# Twintig-FCC-Host.net
KiCad netlist of a schematic drawn in Altium Designer
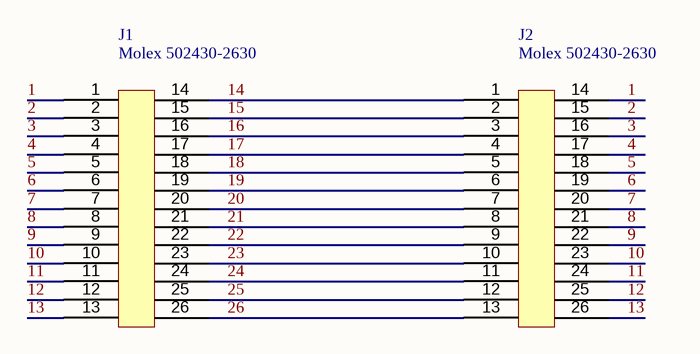
[diagram p0: Twintig-FCC-Host.SchDoc]

(export (version "E")
  (design (tool "Eeschema 10.0.6"))
  (components
    (comp (ref "J1")
      (value "Molex 502430-2630")
      (footprint "Molex 502430-2630")
      (libsource (lib "x-io") (part "Molex 502430-2630"))
    )
    (comp (ref "J2")
      (value "Molex 502430-2630")
      (footprint "Molex 502430-2630")
      (libsource (lib "x-io") (part "Molex 502430-2630"))
    )
  )
  (nets
    (net (code "1") (name "/1") (class "Default")
      (node (ref "J1") (pin "1") (pinfunction "1_1") (pintype "passive"))
      (node (ref "J2") (pin "14") (pinfunction "14_14") (pintype "passive"))
    )
    (net (code "2") (name "/2") (class "Default")
      (node (ref "J1") (pin "2") (pinfunction "2_2") (pintype "passive"))
      (node (ref "J2") (pin "15") (pinfunction "15_15") (pintype "passive"))
    )
    (net (code "3") (name "/3") (class "Default")
      (node (ref "J1") (pin "3") (pinfunction "3_3") (pintype "passive"))
      (node (ref "J2") (pin "16") (pinfunction "16_16") (pintype "passive"))
    )
    (net (code "4") (name "/4") (class "Default")
      (node (ref "J1") (pin "4") (pinfunction "4_4") (pintype "passive"))
      (node (ref "J2") (pin "17") (pinfunction "17_17") (pintype "passive"))
    )
    (net (code "5") (name "/5") (class "Default")
      (node (ref "J1") (pin "5") (pinfunction "5_5") (pintype "passive"))
      (node (ref "J2") (pin "18") (pinfunction "18_18") (pintype "passive"))
    )
    (net (code "6") (name "/6") (class "Default")
      (node (ref "J1") (pin "6") (pinfunction "6_6") (pintype "passive"))
      (node (ref "J2") (pin "19") (pinfunction "19_19") (pintype "passive"))
    )
    (net (code "7") (name "/7") (class "Default")
      (node (ref "J1") (pin "7") (pinfunction "7_7") (pintype "passive"))
      (node (ref "J2") (pin "20") (pinfunction "20_20") (pintype "passive"))
    )
    (net (code "8") (name "/8") (class "Default")
      (node (ref "J1") (pin "8") (pinfunction "8_8") (pintype "passive"))
      (node (ref "J2") (pin "21") (pinfunction "21_21") (pintype "passive"))
    )
    (net (code "9") (name "/9") (class "Default")
      (node (ref "J1") (pin "9") (pinfunction "9_9") (pintype "passive"))
      (node (ref "J2") (pin "22") (pinfunction "22_22") (pintype "passive"))
    )
    (net (code "10") (name "/10") (class "Default")
      (node (ref "J1") (pin "10") (pinfunction "10_10") (pintype "passive"))
      (node (ref "J2") (pin "23") (pinfunction "23_23") (pintype "passive"))
    )
    (net (code "11") (name "/11") (class "Default")
      (node (ref "J1") (pin "11") (pinfunction "11_11") (pintype "passive"))
      (node (ref "J2") (pin "24") (pinfunction "24_24") (pintype "passive"))
    )
    (net (code "12") (name "/12") (class "Default")
      (node (ref "J1") (pin "12") (pinfunction "12_12") (pintype "passive"))
      (node (ref "J2") (pin "25") (pinfunction "25_25") (pintype "passive"))
    )
    (net (code "13") (name "/13") (class "Default")
      (node (ref "J1") (pin "13") (pinfunction "13_13") (pintype "passive"))
      (node (ref "J2") (pin "26") (pinfunction "26_26") (pintype "passive"))
    )
    (net (code "14") (name "/14") (class "Default")
      (node (ref "J1") (pin "14") (pinfunction "14_14") (pintype "passive"))
      (node (ref "J2") (pin "1") (pinfunction "1_1") (pintype "passive"))
    )
    (net (code "15") (name "/15") (class "Default")
      (node (ref "J1") (pin "15") (pinfunction "15_15") (pintype "passive"))
      (node (ref "J2") (pin "2") (pinfunction "2_2") (pintype "passive"))
    )
    (net (code "16") (name "/16") (class "Default")
      (node (ref "J1") (pin "16") (pinfunction "16_16") (pintype "passive"))
      (node (ref "J2") (pin "3") (pinfunction "3_3") (pintype "passive"))
    )
    (net (code "17") (name "/17") (class "Default")
      (node (ref "J1") (pin "17") (pinfunction "17_17") (pintype "passive"))
      (node (ref "J2") (pin "4") (pinfunction "4_4") (pintype "passive"))
    )
    (net (code "18") (name "/18") (class "Default")
      (node (ref "J1") (pin "18") (pinfunction "18_18") (pintype "passive"))
      (node (ref "J2") (pin "5") (pinfunction "5_5") (pintype "passive"))
    )
    (net (code "19") (name "/19") (class "Default")
      (node (ref "J1") (pin "19") (pinfunction "19_19") (pintype "passive"))
      (node (ref "J2") (pin "6") (pinfunction "6_6") (pintype "passive"))
    )
    (net (code "20") (name "/20") (class "Default")
      (node (ref "J1") (pin "20") (pinfunction "20_20") (pintype "passive"))
      (node (ref "J2") (pin "7") (pinfunction "7_7") (pintype "passive"))
    )
    (net (code "21") (name "/21") (class "Default")
      (node (ref "J1") (pin "21") (pinfunction "21_21") (pintype "passive"))
      (node (ref "J2") (pin "8") (pinfunction "8_8") (pintype "passive"))
    )
    (net (code "22") (name "/22") (class "Default")
      (node (ref "J1") (pin "22") (pinfunction "22_22") (pintype "passive"))
      (node (ref "J2") (pin "9") (pinfunction "9_9") (pintype "passive"))
    )
    (net (code "23") (name "/23") (class "Default")
      (node (ref "J1") (pin "23") (pinfunction "23_23") (pintype "passive"))
      (node (ref "J2") (pin "10") (pinfunction "10_10") (pintype "passive"))
    )
    (net (code "24") (name "/24") (class "Default")
      (node (ref "J1") (pin "24") (pinfunction "24_24") (pintype "passive"))
      (node (ref "J2") (pin "11") (pinfunction "11_11") (pintype "passive"))
    )
    (net (code "25") (name "/25") (class "Default")
      (node (ref "J1") (pin "25") (pinfunction "25_25") (pintype "passive"))
      (node (ref "J2") (pin "12") (pinfunction "12_12") (pintype "passive"))
    )
    (net (code "26") (name "/26") (class "Default")
      (node (ref "J1") (pin "26") (pinfunction "26_26") (pintype "passive"))
      (node (ref "J2") (pin "13") (pinfunction "13_13") (pintype "passive"))
    )
  )
)
